# 20A_Motor_Controller_with_SLAVE_OUT.net
KiCad netlist of a schematic drawn in EAGLE
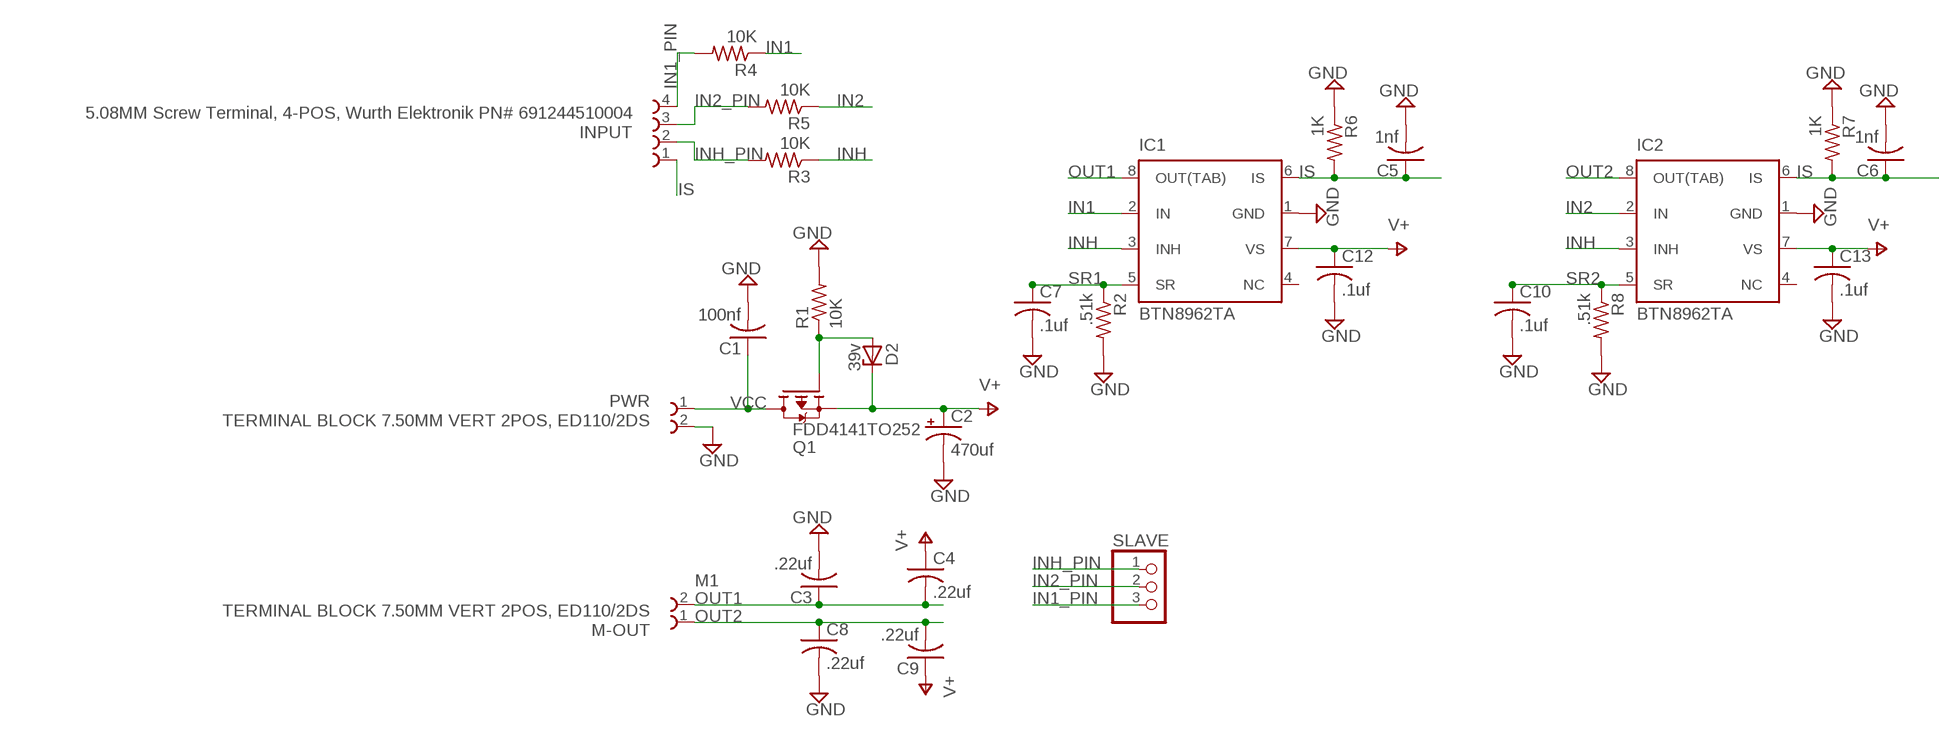
[diagram p0: schematic, sheet 1]

(export (version "E")
  (design (tool "Eeschema 10.0.6"))
  (components
    (comp (ref "C1")
      (value "100nf")
      (footprint "eagle-import:C0805")
      (libsource (lib "eagle-import") (part "C-USC0805"))
    )
    (comp (ref "C2")
      (value "470uf")
      (footprint "eagle-import:TT5D10")
      (libsource (lib "eagle-import") (part "CPOL-USTT5D10"))
    )
    (comp (ref "C3")
      (value ".22uf")
      (footprint "eagle-import:C0805")
      (libsource (lib "eagle-import") (part "C-USC0805"))
    )
    (comp (ref "C4")
      (value ".22uf")
      (footprint "eagle-import:C0805")
      (libsource (lib "eagle-import") (part "C-USC0805"))
    )
    (comp (ref "C5")
      (value "1nf")
      (footprint "eagle-import:C0805")
      (libsource (lib "eagle-import") (part "C-USC0805"))
    )
    (comp (ref "C6")
      (value "1nf")
      (footprint "eagle-import:C0805")
      (libsource (lib "eagle-import") (part "C-USC0805"))
    )
    (comp (ref "C7")
      (value ".1uf")
      (footprint "eagle-import:C0805")
      (libsource (lib "eagle-import") (part "C-USC0805"))
    )
    (comp (ref "C8")
      (value ".22uf")
      (footprint "eagle-import:C0805")
      (libsource (lib "eagle-import") (part "C-USC0805"))
    )
    (comp (ref "C9")
      (value ".22uf")
      (footprint "eagle-import:C0805")
      (libsource (lib "eagle-import") (part "C-USC0805"))
    )
    (comp (ref "C10")
      (value ".1uf")
      (footprint "eagle-import:C0805")
      (libsource (lib "eagle-import") (part "C-USC0805"))
    )
    (comp (ref "C12")
      (value ".1uf")
      (footprint "eagle-import:C0805")
      (libsource (lib "eagle-import") (part "C-USC0805"))
    )
    (comp (ref "C13")
      (value ".1uf")
      (footprint "eagle-import:C0805")
      (libsource (lib "eagle-import") (part "C-USC0805"))
    )
    (comp (ref "D2")
      (value "39v")
      (footprint "eagle-import:SMB")
      (libsource (lib "eagle-import") (part "ZENER-DIODESMB"))
    )
    (comp (ref "IC1")
      (value "BTN8962TA")
      (footprint "eagle-import:P-TO263-7-1_LG_PADS")
      (libsource (lib "eagle-import") (part "BTN8962TA"))
    )
    (comp (ref "IC2")
      (value "BTN8962TA")
      (footprint "eagle-import:P-TO263-7-1_LG_PADS")
      (libsource (lib "eagle-import") (part "BTN8962TA"))
    )
    (comp (ref "INPUT")
      (value "5.08MM Screw Terminal, 4-POS, Wurth Elektronik PN# 691244510004")
      (footprint "eagle-import:691244510004")
      (libsource (lib "eagle-import") (part "691244510004"))
    )
    (comp (ref "M-OUT")
      (value "TERMINAL BLOCK 7.50MM VERT 2POS, ED110/2DS")
      (footprint "eagle-import:7-5MM-SCREW-TERM")
      (libsource (lib "eagle-import") (part "7-5MM-SCREW-TERM"))
    )
    (comp (ref "PWR")
      (value "TERMINAL BLOCK 7.50MM VERT 2POS, ED110/2DS")
      (footprint "eagle-import:7-5MM-SCREW-TERM")
      (libsource (lib "eagle-import") (part "7-5MM-SCREW-TERM"))
    )
    (comp (ref "Q1")
      (value "FDD4141TO252")
      (footprint "eagle-import:TO252")
      (libsource (lib "eagle-import") (part "FDD4141TO252"))
    )
    (comp (ref "R1")
      (value "10K")
      (footprint "eagle-import:R0805")
      (libsource (lib "eagle-import") (part "R-US_R0805"))
    )
    (comp (ref "R2")
      (value ".51k")
      (footprint "eagle-import:R0805")
      (libsource (lib "eagle-import") (part "R-US_R0805"))
    )
    (comp (ref "R3")
      (value "10K")
      (footprint "eagle-import:R0805")
      (libsource (lib "eagle-import") (part "R-US_R0805"))
    )
    (comp (ref "R4")
      (value "10K")
      (footprint "eagle-import:R0805")
      (libsource (lib "eagle-import") (part "R-US_R0805"))
    )
    (comp (ref "R5")
      (value "10K")
      (footprint "eagle-import:R0805")
      (libsource (lib "eagle-import") (part "R-US_R0805"))
    )
    (comp (ref "R6")
      (value "1K")
      (footprint "eagle-import:R0805")
      (libsource (lib "eagle-import") (part "R-US_R0805"))
    )
    (comp (ref "R7")
      (value "1K")
      (footprint "eagle-import:R0805")
      (libsource (lib "eagle-import") (part "R-US_R0805"))
    )
    (comp (ref "R8")
      (value ".51k")
      (footprint "eagle-import:R0805")
      (libsource (lib "eagle-import") (part "R-US_R0805"))
    )
    (comp (ref "SLAVE")
      (value "PINHD-1X3CB")
      (footprint "eagle-import:1X03-CLEANBIG")
      (libsource (lib "eagle-import") (part "PINHD-1X3CB"))
    )
  )
  (nets
    (net (code "1") (name "/IN1") (class "Default")
      (node (ref "IC1") (pin "2") (pinfunction "IN_2") (pintype "input"))
      (node (ref "R4") (pin "1") (pinfunction "1_1") (pintype "passive"))
    )
    (net (code "2") (name "/IN1_PIN") (class "Default")
      (node (ref "INPUT") (pin "4") (pinfunction "4_4") (pintype "passive"))
      (node (ref "R4") (pin "2") (pinfunction "2_2") (pintype "passive"))
      (node (ref "SLAVE") (pin "3") (pinfunction "3_3") (pintype "passive"))
    )
    (net (code "3") (name "/IN2") (class "Default")
      (node (ref "IC2") (pin "2") (pinfunction "IN_2") (pintype "input"))
      (node (ref "R5") (pin "1") (pinfunction "1_1") (pintype "passive"))
    )
    (net (code "4") (name "/IN2_PIN") (class "Default")
      (node (ref "INPUT") (pin "3") (pinfunction "3_3") (pintype "passive"))
      (node (ref "R5") (pin "2") (pinfunction "2_2") (pintype "passive"))
      (node (ref "SLAVE") (pin "2") (pinfunction "2_2") (pintype "passive"))
    )
    (net (code "5") (name "/INH") (class "Default")
      (node (ref "IC1") (pin "3") (pinfunction "INH_3") (pintype "input"))
      (node (ref "IC2") (pin "3") (pinfunction "INH_3") (pintype "input"))
      (node (ref "R3") (pin "1") (pinfunction "1_1") (pintype "passive"))
    )
    (net (code "6") (name "/INH_PIN") (class "Default")
      (node (ref "INPUT") (pin "2") (pinfunction "2_2") (pintype "passive"))
      (node (ref "R3") (pin "2") (pinfunction "2_2") (pintype "passive"))
      (node (ref "SLAVE") (pin "1") (pinfunction "1_1") (pintype "passive"))
    )
    (net (code "7") (name "/IS") (class "Default")
      (node (ref "C5") (pin "1") (pinfunction "1_1") (pintype "passive"))
      (node (ref "C6") (pin "1") (pinfunction "1_1") (pintype "passive"))
      (node (ref "IC1") (pin "6") (pinfunction "IS_6") (pintype "output"))
      (node (ref "IC2") (pin "6") (pinfunction "IS_6") (pintype "output"))
      (node (ref "INPUT") (pin "1") (pinfunction "1_1") (pintype "passive"))
      (node (ref "R6") (pin "2") (pinfunction "2_2") (pintype "passive"))
      (node (ref "R7") (pin "2") (pinfunction "2_2") (pintype "passive"))
    )
    (net (code "8") (name "/OUT1") (class "Default")
      (node (ref "C3") (pin "1") (pinfunction "1_1") (pintype "passive"))
      (node (ref "C4") (pin "2") (pinfunction "2_2") (pintype "passive"))
      (node (ref "IC1") (pin "8") (pinfunction "OUT(TAB)_8") (pintype "output"))
      (node (ref "M-OUT") (pin "2") (pinfunction "2_2") (pintype "passive"))
    )
    (net (code "9") (name "/OUT2") (class "Default")
      (node (ref "C8") (pin "1") (pinfunction "1_1") (pintype "passive"))
      (node (ref "C9") (pin "2") (pinfunction "2_2") (pintype "passive"))
      (node (ref "IC2") (pin "8") (pinfunction "OUT(TAB)_8") (pintype "output"))
      (node (ref "M-OUT") (pin "1") (pinfunction "1_1") (pintype "passive"))
    )
    (net (code "10") (name "/SR1") (class "Default")
      (node (ref "C7") (pin "1") (pinfunction "1_1") (pintype "passive"))
      (node (ref "IC1") (pin "5") (pinfunction "SR_5") (pintype "input"))
      (node (ref "R2") (pin "1") (pinfunction "1_1") (pintype "passive"))
    )
    (net (code "11") (name "/SR2") (class "Default")
      (node (ref "C10") (pin "1") (pinfunction "1_1") (pintype "passive"))
      (node (ref "IC2") (pin "5") (pinfunction "SR_5") (pintype "input"))
      (node (ref "R8") (pin "1") (pinfunction "1_1") (pintype "passive"))
    )
    (net (code "12") (name "/VCC") (class "Default")
      (node (ref "C1") (pin "1") (pinfunction "1_1") (pintype "passive"))
      (node (ref "PWR") (pin "1") (pinfunction "1_1") (pintype "passive"))
      (node (ref "Q1") (pin "3") (pinfunction "D_3") (pintype "passive"))
    )
    (net (code "13") (name "GND") (class "Default")
      (node (ref "C1") (pin "2") (pinfunction "2_2") (pintype "passive"))
      (node (ref "C10") (pin "2") (pinfunction "2_2") (pintype "passive"))
      (node (ref "C12") (pin "2") (pinfunction "2_2") (pintype "passive"))
      (node (ref "C13") (pin "2") (pinfunction "2_2") (pintype "passive"))
      (node (ref "C2") (pin "-") (pinfunction "-_-") (pintype "passive"))
      (node (ref "C3") (pin "2") (pinfunction "2_2") (pintype "passive"))
      (node (ref "C5") (pin "2") (pinfunction "2_2") (pintype "passive"))
      (node (ref "C6") (pin "2") (pinfunction "2_2") (pintype "passive"))
      (node (ref "C7") (pin "2") (pinfunction "2_2") (pintype "passive"))
      (node (ref "C8") (pin "2") (pinfunction "2_2") (pintype "passive"))
      (node (ref "IC1") (pin "1") (pinfunction "GND_1") (pintype "power_in"))
      (node (ref "IC2") (pin "1") (pinfunction "GND_1") (pintype "power_in"))
      (node (ref "PWR") (pin "2") (pinfunction "2_2") (pintype "passive"))
      (node (ref "R1") (pin "2") (pinfunction "2_2") (pintype "passive"))
      (node (ref "R2") (pin "2") (pinfunction "2_2") (pintype "passive"))
      (node (ref "R6") (pin "1") (pinfunction "1_1") (pintype "passive"))
      (node (ref "R7") (pin "1") (pinfunction "1_1") (pintype "passive"))
      (node (ref "R8") (pin "2") (pinfunction "2_2") (pintype "passive"))
    )
    (net (code "14") (name "Net-(Q1-G)") (class "Default")
      (node (ref "D2") (pin "A") (pinfunction "A_A") (pintype "passive"))
      (node (ref "Q1") (pin "1") (pinfunction "G_1") (pintype "passive"))
      (node (ref "R1") (pin "1") (pinfunction "1_1") (pintype "passive"))
    )
    (net (code "15") (name "V+") (class "Default")
      (node (ref "C12") (pin "1") (pinfunction "1_1") (pintype "passive"))
      (node (ref "C13") (pin "1") (pinfunction "1_1") (pintype "passive"))
      (node (ref "C2") (pin "+") (pinfunction "+_+") (pintype "passive"))
      (node (ref "C4") (pin "1") (pinfunction "1_1") (pintype "passive"))
      (node (ref "C9") (pin "1") (pinfunction "1_1") (pintype "passive"))
      (node (ref "D2") (pin "C") (pinfunction "C_C") (pintype "passive"))
      (node (ref "IC1") (pin "7") (pinfunction "VS_7") (pintype "power_in"))
      (node (ref "IC2") (pin "7") (pinfunction "VS_7") (pintype "power_in"))
      (node (ref "Q1") (pin "2") (pinfunction "S_2") (pintype "passive"))
    )
    (net (code "16") (name "unconnected-(IC1-NC-Pad4)") (class "Default")
      (node (ref "IC1") (pin "4") (pinfunction "NC_4") (pintype "no_connect"))
    )
    (net (code "17") (name "unconnected-(IC2-NC-Pad4)") (class "Default")
      (node (ref "IC2") (pin "4") (pinfunction "NC_4") (pintype "no_connect"))
    )
  )
)
